# dac.net
KiCad netlist of a schematic drawn in Altium Designer
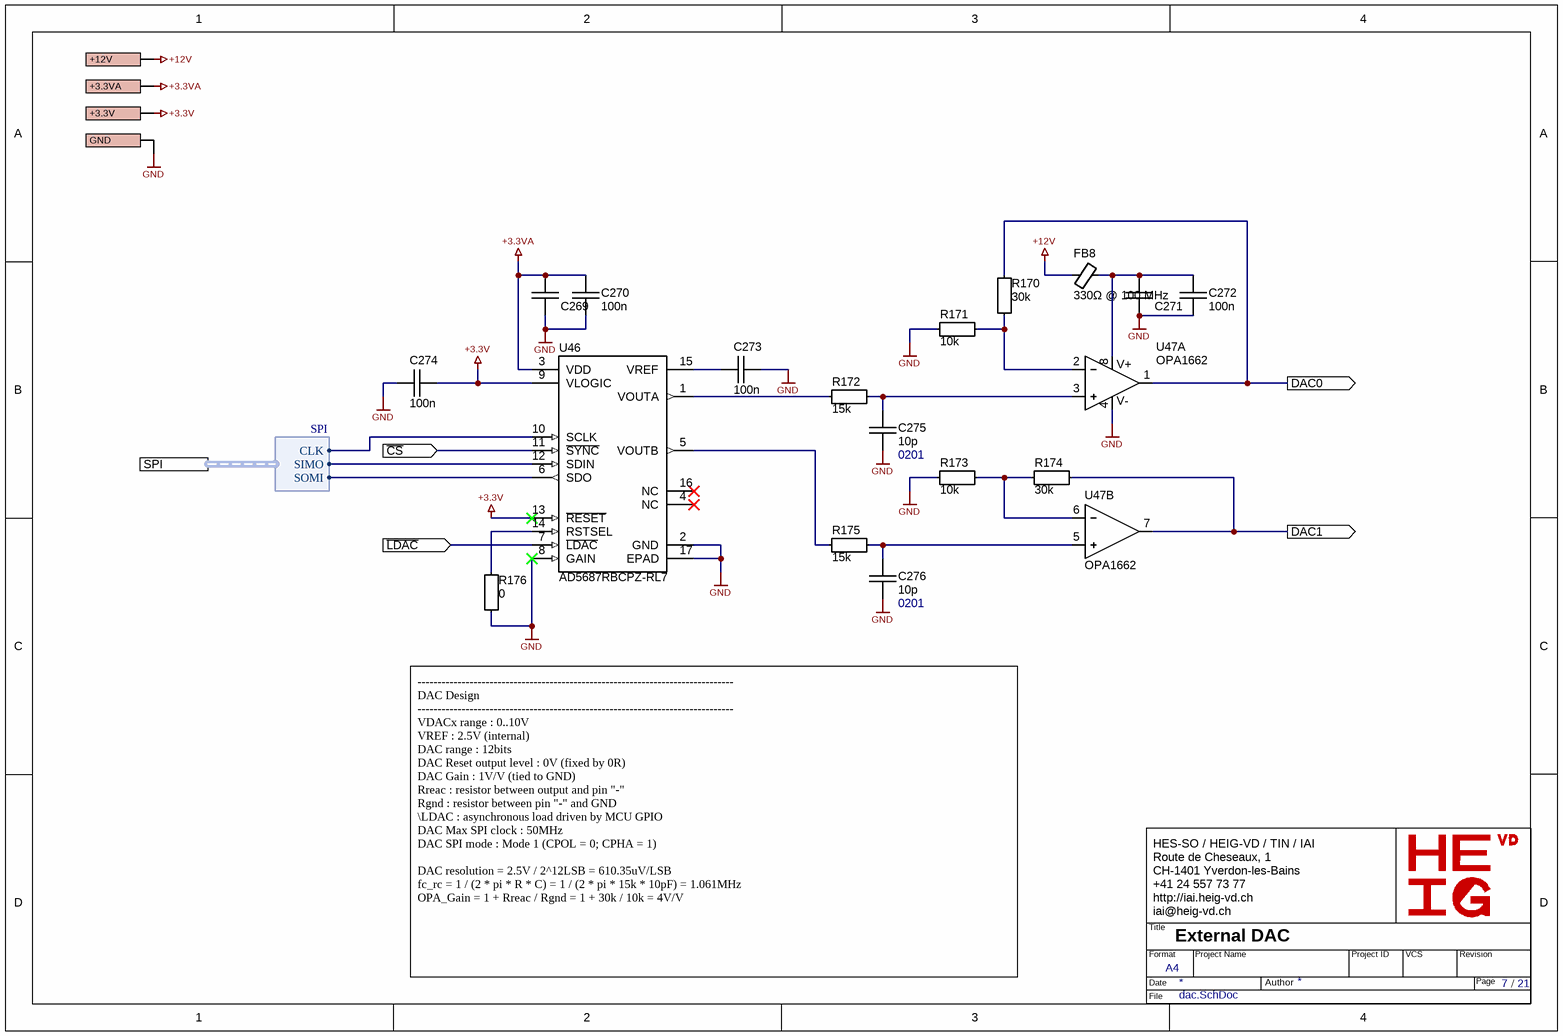
[diagram p0: dac.SchDoc]

(export (version "E")
  (design (tool "Eeschema 10.0.6"))
  (components
    (comp (ref "C269")
      (value "10u")
      (footprint "SM/C0402")
      (description "10 µF ±20% 6.3V Ceramic Capacitor X5R 0402 (1005 Metric)")
      (fields (field (name "VOLTAGE") "6.3V"))
      (libsource (lib "motionboard") (part "CAP CER 10UF 6.3V X5R 0402"))
    )
    (comp (ref "C270")
      (value "100n")
      (footprint "SM/C0402")
      (description "100 nF ±10% 25V Ceramic Capacitor X5R 0402 (1005 Metric)")
      (fields (field (name "VOLTAGE") "25V"))
      (libsource (lib "motionboard") (part "CAP CER 100NF 25V X5R 0402"))
    )
    (comp (ref "C271")
      (value "10u")
      (footprint "SM/C0402")
      (description "10 µF ±20% 6.3V Ceramic Capacitor X5R 0402 (1005 Metric)")
      (fields (field (name "VOLTAGE") "6.3V"))
      (libsource (lib "motionboard") (part "CAP CER 10UF 6.3V X5R 0402"))
    )
    (comp (ref "C272")
      (value "100n")
      (footprint "SM/C0402")
      (description "100 nF ±10% 25V Ceramic Capacitor X5R 0402 (1005 Metric)")
      (fields (field (name "VOLTAGE") "25V"))
      (libsource (lib "motionboard") (part "CAP CER 100NF 25V X5R 0402"))
    )
    (comp (ref "C273")
      (value "100n")
      (footprint "SM/C0402")
      (description "100 nF ±10% 25V Ceramic Capacitor X5R 0402 (1005 Metric)")
      (fields (field (name "VOLTAGE") "25V"))
      (libsource (lib "motionboard") (part "CAP CER 100NF 25V X5R 0402"))
    )
    (comp (ref "C274")
      (value "100n")
      (footprint "SM/C0402")
      (description "100 nF ±10% 25V Ceramic Capacitor X5R 0402 (1005 Metric)")
      (fields (field (name "VOLTAGE") "25V"))
      (libsource (lib "motionboard") (part "CAP CER 100NF 25V X5R 0402"))
    )
    (comp (ref "C275")
      (value "10p")
      (footprint "SM/C0201")
      (description "10 pF ±5% 25V Ceramic Capacitor C0G, NP0 0201 (0603 Metric)")
      (fields (field (name "VOLTAGE") "25V") (field (name "CASE") "0201"))
      (libsource (lib "motionboard") (part "CAP CER 10PF 25V C0G/NP0 0201"))
    )
    (comp (ref "C276")
      (value "10p")
      (footprint "SM/C0201")
      (description "10 pF ±5% 25V Ceramic Capacitor C0G, NP0 0201 (0603 Metric)")
      (fields (field (name "VOLTAGE") "25V") (field (name "CASE") "0201"))
      (libsource (lib "motionboard") (part "CAP CER 10PF 25V C0G/NP0 0201"))
    )
    (comp (ref "FB8")
      (value "330Ω @ 100 MHz")
      (footprint "SM/L0603")
      (description "330 Ohms @ 100 MHz 1 Power Line Ferrite Bead 0603 (1608 Metric) 1.7A 80mOhm")
      (fields (field (name "Comment") "BLM18KG331SN1D"))
      (libsource (lib "motionboard") (part "FERRITE BEAD 330 OHM 0603 1LN"))
    )
    (comp (ref "R170")
      (value "30k")
      (footprint "SM/R0402")
      (description "30 kOhms ±1% 0.063W, 1/16W Chip Resistor 0402 (1005 Metric) Moisture Resistant Thick Film")
      (libsource (lib "motionboard") (part "RES 30K OHM 1% 1/16W 0402"))
    )
    (comp (ref "R171")
      (value "10k")
      (footprint "SM/R0402")
      (description "10 kOhms ±1% 0.063W, 1/16W Chip Resistor 0402 (1005 Metric) Moisture Resistant Thick Film")
      (libsource (lib "motionboard") (part "RES 10K OHM 1% 1/16W 0402"))
    )
    (comp (ref "R172")
      (value "15k")
      (footprint "SM/R0402")
      (description "15 kOhms ±1% 0.063W, 1/16W Chip Resistor 0402 (1005 Metric) Thick Film")
      (libsource (lib "motionboard") (part "RES 15K OHM 1% 1/16W 0402"))
    )
    (comp (ref "R173")
      (value "10k")
      (footprint "SM/R0402")
      (description "10 kOhms ±1% 0.063W, 1/16W Chip Resistor 0402 (1005 Metric) Moisture Resistant Thick Film")
      (libsource (lib "motionboard") (part "RES 10K OHM 1% 1/16W 0402"))
    )
    (comp (ref "R174")
      (value "30k")
      (footprint "SM/R0402")
      (description "30 kOhms ±1% 0.063W, 1/16W Chip Resistor 0402 (1005 Metric) Moisture Resistant Thick Film")
      (libsource (lib "") (part "RES 30K OHM 1% 1/16W 0402_1"))
    )
    (comp (ref "R175")
      (value "15k")
      (footprint "SM/R0402")
      (description "15 kOhms ±1% 0.063W, 1/16W Chip Resistor 0402 (1005 Metric) Thick Film")
      (libsource (lib "motionboard") (part "RES 15K OHM 1% 1/16W 0402"))
    )
    (comp (ref "R176")
      (value "0")
      (footprint "SM/R0402")
      (description "0 Ohms Jumper Chip Resistor 0402 (1005 Metric) Automotive AEC-Q200 Thick Film")
      (libsource (lib "motionboard") (part "RES SMD 0 OHM JUMPER 1/10W 0402"))
    )
    (comp (ref "U46")
      (value "AD5687RBCPZ-RL7")
      (footprint "QFN50P300X300X80_HS-17N")
      (description "12 Bit Digital to Analog Converter 2 16-LFCSP (3x3)")
      (libsource (lib "motionboard") (part "AD5687RBCPZ-RL7"))
    )
    (comp (ref "U47")
      (value "OPA1662")
      (footprint "SOIC8")
      (description "Dual operational amplifier")
      (libsource (lib "motionboard") (part "OPA1662"))
    )
  )
  (nets
    (net (code "2") (name "+3.3V") (class "Default")
      (node (ref "C274") (pin "1") (pintype "passive"))
      (node (ref "U46") (pin "13") (pinfunction "RESET_13") (pintype "input"))
      (node (ref "U46") (pin "9") (pinfunction "VLOGIC_9") (pintype "power_in"))
    )
    (net (code "3") (name "+3.3VA") (class "Default")
      (node (ref "C269") (pin "1") (pintype "passive"))
      (node (ref "C270") (pin "1") (pintype "passive"))
      (node (ref "U46") (pin "3") (pinfunction "VDD_3") (pintype "power_in"))
    )
    (net (code "4") (name "+12V") (class "Default")
      (node (ref "FB8") (pin "1") (pinfunction "1_1") (pintype "passive"))
    )
    (net (code "5") (name "/CLK") (class "Default")
      (node (ref "U46") (pin "10") (pinfunction "SCLK_10") (pintype "input"))
    )
    (net (code "6") (name "/CS") (class "Default")
      (node (ref "U46") (pin "11") (pinfunction "SYNC_11") (pintype "input"))
    )
    (net (code "7") (name "/DAC0") (class "Default")
      (node (ref "R170") (pin "2") (pintype "passive"))
      (node (ref "U47") (pin "1") (pinfunction "OUT_1") (pintype "passive"))
    )
    (net (code "8") (name "/DAC1") (class "Default")
      (node (ref "R174") (pin "2") (pintype "passive"))
      (node (ref "U47") (pin "7") (pinfunction "OUT_7") (pintype "passive"))
    )
    (net (code "9") (name "/LDAC") (class "Default")
      (node (ref "U46") (pin "7") (pinfunction "LDAC_7") (pintype "input"))
    )
    (net (code "10") (name "/SIMO") (class "Default")
      (node (ref "U46") (pin "12") (pinfunction "SDIN_12") (pintype "input"))
    )
    (net (code "11") (name "/SOMI") (class "Default")
      (node (ref "U46") (pin "6") (pinfunction "SDO_6") (pintype "output"))
    )
    (net (code "13") (name "GND") (class "Default")
      (node (ref "C269") (pin "2") (pintype "passive"))
      (node (ref "C270") (pin "2") (pintype "passive"))
      (node (ref "C271") (pin "2") (pintype "passive"))
      (node (ref "C272") (pin "2") (pintype "passive"))
      (node (ref "C273") (pin "2") (pintype "passive"))
      (node (ref "C274") (pin "2") (pintype "passive"))
      (node (ref "C275") (pin "2") (pintype "passive"))
      (node (ref "C276") (pin "2") (pintype "passive"))
      (node (ref "R171") (pin "1") (pintype "passive"))
      (node (ref "R173") (pin "1") (pintype "passive"))
      (node (ref "R176") (pin "1") (pintype "passive"))
      (node (ref "U46") (pin "17") (pinfunction "EPAD_17") (pintype "passive"))
      (node (ref "U46") (pin "2") (pinfunction "GND_2") (pintype "power_in"))
      (node (ref "U46") (pin "8") (pinfunction "GAIN_8") (pintype "input"))
      (node (ref "U47") (pin "4") (pinfunction "V-_4") (pintype "passive"))
    )
    (net (code "14") (name "Net-(U46-RSTSEL)") (class "Default")
      (node (ref "R176") (pin "2") (pintype "passive"))
      (node (ref "U46") (pin "14") (pinfunction "RSTSEL_14") (pintype "input"))
    )
    (net (code "15") (name "Net-(U46-VOUTA)") (class "Default")
      (node (ref "R172") (pin "1") (pintype "passive"))
      (node (ref "U46") (pin "1") (pinfunction "VOUTA_1") (pintype "output"))
    )
    (net (code "16") (name "Net-(U46-VOUTB)") (class "Default")
      (node (ref "R175") (pin "1") (pintype "passive"))
      (node (ref "U46") (pin "5") (pinfunction "VOUTB_5") (pintype "output"))
    )
    (net (code "17") (name "Net-(U46-VREF)") (class "Default")
      (node (ref "C273") (pin "1") (pintype "passive"))
      (node (ref "U46") (pin "15") (pinfunction "VREF_15") (pintype "passive"))
    )
    (net (code "18") (name "Net-(U47A-IN+)") (class "Default")
      (node (ref "C275") (pin "1") (pintype "passive"))
      (node (ref "R172") (pin "2") (pintype "passive"))
      (node (ref "U47") (pin "3") (pinfunction "IN+_3") (pintype "passive"))
    )
    (net (code "19") (name "Net-(U47A-IN-)") (class "Default")
      (node (ref "R170") (pin "1") (pintype "passive"))
      (node (ref "R171") (pin "2") (pintype "passive"))
      (node (ref "U47") (pin "2") (pinfunction "IN-_2") (pintype "passive"))
    )
    (net (code "20") (name "Net-(U47A-V+)") (class "Default")
      (node (ref "C271") (pin "1") (pintype "passive"))
      (node (ref "C272") (pin "1") (pintype "passive"))
      (node (ref "FB8") (pin "2") (pinfunction "2_2") (pintype "passive"))
      (node (ref "U47") (pin "8") (pinfunction "V+_8") (pintype "passive"))
    )
    (net (code "21") (name "Net-(U47B-IN+)") (class "Default")
      (node (ref "C276") (pin "1") (pintype "passive"))
      (node (ref "R175") (pin "2") (pintype "passive"))
      (node (ref "U47") (pin "5") (pinfunction "IN+_5") (pintype "passive"))
    )
    (net (code "22") (name "Net-(U47B-IN-)") (class "Default")
      (node (ref "R173") (pin "2") (pintype "passive"))
      (node (ref "R174") (pin "1") (pintype "passive"))
      (node (ref "U47") (pin "6") (pinfunction "IN-_6") (pintype "passive"))
    )
    (net (code "23") (name "unconnected-(U46-NC-Pad4)") (class "Default")
      (node (ref "U46") (pin "4") (pinfunction "NC_4") (pintype "passive+no_connect"))
    )
    (net (code "24") (name "unconnected-(U46-NC-Pad16)") (class "Default")
      (node (ref "U46") (pin "16") (pinfunction "NC_16") (pintype "passive+no_connect"))
    )
  )
)
